# attiny_breakout_ISP6.net
KiCad netlist of a schematic drawn in EAGLE
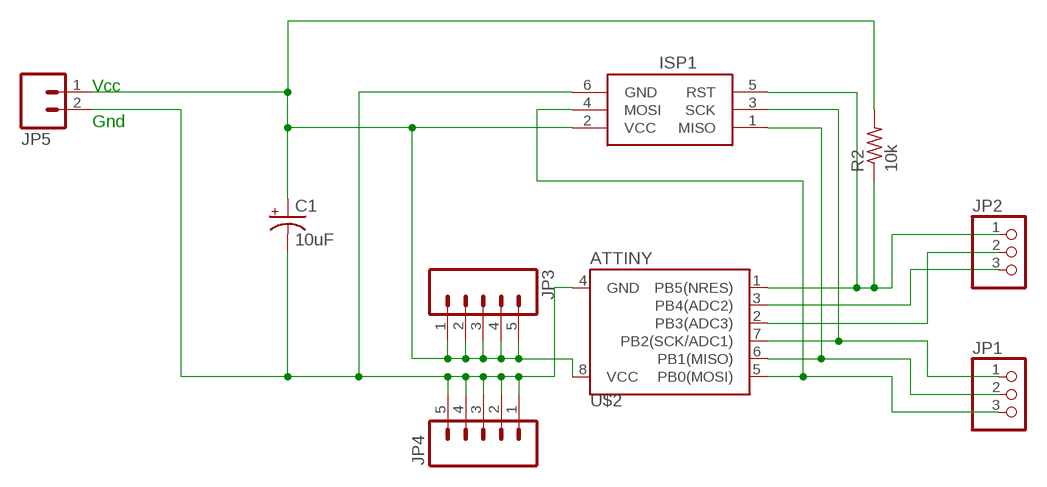
[diagram p0: schematic, sheet 1]

(export (version "E")
  (design (tool "Eeschema 10.0.6"))
  (components
    (comp (ref "C1")
      (value "10uF")
      (footprint "eagle-import:CPOL-RADIAL-10UF-25V")
      (libsource (lib "eagle-import") (part "CAP_POLPTH2"))
    )
    (comp (ref "ISP1")
      (value "AVRISP-6")
      (footprint "eagle-import:AVRISP")
      (libsource (lib "eagle-import") (part "AVRISP-6"))
    )
    (comp (ref "JP1")
      (value "PINHD-1X3")
      (footprint "eagle-import:1X03")
      (libsource (lib "eagle-import") (part "PINHD-1X3"))
    )
    (comp (ref "JP2")
      (value "PINHD-1X3")
      (footprint "eagle-import:1X03")
      (libsource (lib "eagle-import") (part "PINHD-1X3"))
    )
    (comp (ref "JP3")
      (value "M05PTH")
      (footprint "eagle-import:1X05")
      (libsource (lib "eagle-import") (part "M05PTH"))
    )
    (comp (ref "JP4")
      (value "M05PTH")
      (footprint "eagle-import:1X05")
      (libsource (lib "eagle-import") (part "M05PTH"))
    )
    (comp (ref "JP5")
      (value "M02PTH")
      (footprint "eagle-import:1X02")
      (libsource (lib "eagle-import") (part "M02PTH"))
    )
    (comp (ref "R2")
      (value "10k")
      (footprint "eagle-import:0207_12")
      (libsource (lib "eagle-import") (part "R-US_0207/12"))
    )
    (comp (ref "U$2")
      (value "ATTINY")
      (footprint "eagle-import:DIP08")
      (libsource (lib "eagle-import") (part "ATTINY13DIP"))
    )
  )
  (nets
    (net (code "1") (name "Net-(C1-+)") (class "Default")
      (node (ref "C1") (pin "1") (pinfunction "+_1") (pintype "passive"))
      (node (ref "ISP1") (pin "2") (pinfunction "VCC_2") (pintype "power_in"))
      (node (ref "JP3") (pin "1") (pinfunction "1_1") (pintype "passive"))
      (node (ref "JP3") (pin "2") (pinfunction "2_2") (pintype "passive"))
      (node (ref "JP3") (pin "3") (pinfunction "3_3") (pintype "passive"))
      (node (ref "JP3") (pin "4") (pinfunction "4_4") (pintype "passive"))
      (node (ref "JP3") (pin "5") (pinfunction "5_5") (pintype "passive"))
      (node (ref "JP5") (pin "1") (pinfunction "1_1") (pintype "passive"))
      (node (ref "R2") (pin "2") (pinfunction "2_2") (pintype "passive"))
      (node (ref "U$2") (pin "8") (pinfunction "VCC_8") (pintype "bidirectional"))
    )
    (net (code "2") (name "Net-(C1--)") (class "Default")
      (node (ref "C1") (pin "2") (pinfunction "-_2") (pintype "passive"))
      (node (ref "ISP1") (pin "6") (pinfunction "GND_6") (pintype "power_in"))
      (node (ref "JP4") (pin "1") (pinfunction "1_1") (pintype "passive"))
      (node (ref "JP4") (pin "2") (pinfunction "2_2") (pintype "passive"))
      (node (ref "JP4") (pin "3") (pinfunction "3_3") (pintype "passive"))
      (node (ref "JP4") (pin "4") (pinfunction "4_4") (pintype "passive"))
      (node (ref "JP4") (pin "5") (pinfunction "5_5") (pintype "passive"))
      (node (ref "JP5") (pin "2") (pinfunction "2_2") (pintype "passive"))
      (node (ref "U$2") (pin "4") (pinfunction "GND_4") (pintype "bidirectional"))
    )
    (net (code "3") (name "Net-(ISP1-MISO)") (class "Default")
      (node (ref "ISP1") (pin "1") (pinfunction "MISO_1") (pintype "input"))
      (node (ref "JP1") (pin "2") (pinfunction "2_2") (pintype "passive"))
      (node (ref "U$2") (pin "6") (pinfunction "PB1(MISO)_6") (pintype "bidirectional"))
    )
    (net (code "4") (name "Net-(ISP1-MOSI)") (class "Default")
      (node (ref "ISP1") (pin "4") (pinfunction "MOSI_4") (pintype "output"))
      (node (ref "JP1") (pin "3") (pinfunction "3_3") (pintype "passive"))
      (node (ref "U$2") (pin "5") (pinfunction "PB0(MOSI)_5") (pintype "bidirectional"))
    )
    (net (code "5") (name "Net-(ISP1-RST)") (class "Default")
      (node (ref "ISP1") (pin "5") (pinfunction "RST_5") (pintype "output"))
      (node (ref "JP2") (pin "1") (pinfunction "1_1") (pintype "passive"))
      (node (ref "R2") (pin "1") (pinfunction "1_1") (pintype "passive"))
      (node (ref "U$2") (pin "1") (pinfunction "PB5(NRES)_1") (pintype "bidirectional"))
    )
    (net (code "6") (name "Net-(ISP1-SCK)") (class "Default")
      (node (ref "ISP1") (pin "3") (pinfunction "SCK_3") (pintype "output"))
      (node (ref "JP1") (pin "1") (pinfunction "1_1") (pintype "passive"))
      (node (ref "U$2") (pin "7") (pinfunction "PB2(SCK/ADC1)_7") (pintype "bidirectional"))
    )
    (net (code "7") (name "Net-(U$2-PB3(ADC3))") (class "Default")
      (node (ref "JP2") (pin "2") (pinfunction "2_2") (pintype "passive"))
      (node (ref "U$2") (pin "2") (pinfunction "PB3(ADC3)_2") (pintype "bidirectional"))
    )
    (net (code "8") (name "Net-(U$2-PB4(ADC2))") (class "Default")
      (node (ref "JP2") (pin "3") (pinfunction "3_3") (pintype "passive"))
      (node (ref "U$2") (pin "3") (pinfunction "PB4(ADC2)_3") (pintype "bidirectional"))
    )
  )
)
